# LDO.net
KiCad netlist of a schematic drawn in Altium Designer
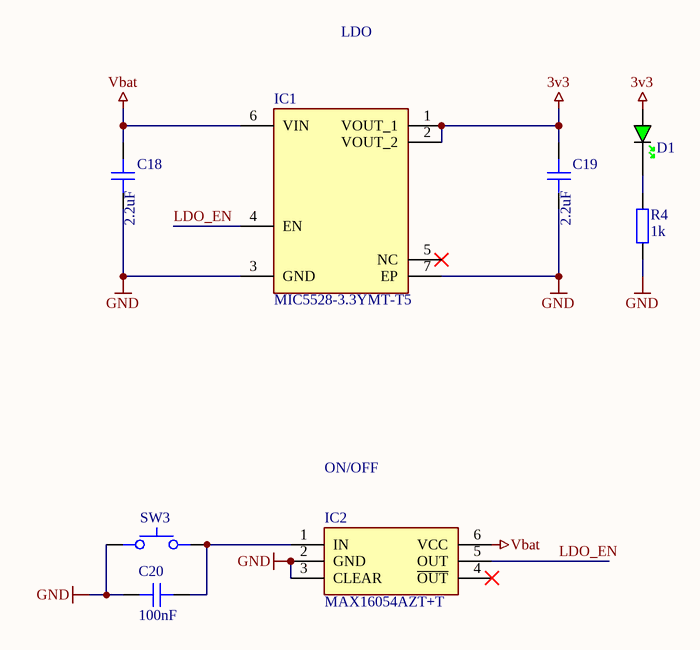
[diagram p0: LDO.SchDoc]

(export (version "E")
  (design (tool "Eeschema 10.0.6"))
  (components
    (comp (ref "C18")
      (value "2.2uF")
      (footprint "CAP_0402")
      (description "Capacitor SMD 0402 10V")
      (fields (field (name "Comment") "C0402_10V"))
      (libsource (lib "Schematic-Lib-PhilsLab") (part "CAP_0402_10V"))
    )
    (comp (ref "C19")
      (value "2.2uF")
      (footprint "CAP_0402")
      (description "Capacitor SMD 0402 10V")
      (fields (field (name "Comment") "C0402_10V"))
      (libsource (lib "Schematic-Lib-PhilsLab") (part "CAP_0402_10V"))
    )
    (comp (ref "C20")
      (value "100nF")
      (footprint "CAP_0402")
      (description "Capacitor SMD 0402 10V")
      (fields (field (name "Comment") "C0402_10V"))
      (libsource (lib "Schematic-Lib-PhilsLab") (part "CAP_0402_10V"))
    )
    (comp (ref "D1")
      (value "GREEN")
      (footprint "LED_0402_GREEN")
      (description "LED 0402 GREEN SMD")
      (libsource (lib "Schematic-Lib-PhilsLab") (part "LED_0402_GREEN"))
    )
    (comp (ref "IC1")
      (value "MIC5528-3.3YMT-T5")
      (footprint "Footprint-Lib-PhilsLab:SON40P120X120X60-7N-D")
      (description "LDO 3v3 500mA")
      (fields (field (name "MOUSER PART NUMBER") "998-MIC5528-3.3YMTT5"))
      (libsource (lib "Schematic-Lib-PhilsLab") (part "MIC5528-3.3YMT-T5"))
    )
    (comp (ref "IC2")
      (value "MAX16054AZT+T")
      (footprint "Footprint-Lib-PhilsLab:SOT95P275X110-6N")
      (description "Integrated Circuit")
      (fields (field (name "MOUSER PART NUMBER") "700-MAX16054AZTT"))
      (libsource (lib "Schematic-Lib-PhilsLab") (part "MAX16054AZT+T"))
    )
    (comp (ref "R4")
      (value "1k")
      (footprint "RES_0402")
      (description "Resistor SMD 0402")
      (fields (field (name "Comment") "R0402"))
      (libsource (lib "Schematic-Lib-PhilsLab") (part "RES_0402"))
    )
    (comp (ref "SW3")
      (value "SKRPANE010")
      (footprint "SKRPANE010")
      (description "Tactile Switch SMD SPST")
      (fields (field (name "MANUFACTURER") "Alps Alpine"))
      (libsource (lib "Schematic-Lib-PhilsLab") (part "SKRPANE010"))
    )
  )
  (nets
    (net (code "1") (name "/LDO_EN") (class "Default")
      (node (ref "IC1") (pin "4") (pinfunction "EN_4") (pintype "passive"))
      (node (ref "IC2") (pin "5") (pinfunction "OUT_5") (pintype "passive"))
    )
    (net (code "2") (name "3v3") (class "Default")
      (node (ref "C19") (pin "2") (pinfunction "2_2") (pintype "passive"))
      (node (ref "D1") (pin "A") (pinfunction "A_A") (pintype "passive"))
      (node (ref "IC1") (pin "1") (pinfunction "VOUT_1_1") (pintype "passive"))
      (node (ref "IC1") (pin "2") (pinfunction "VOUT_2_2") (pintype "passive"))
    )
    (net (code "3") (name "GND") (class "Default")
      (node (ref "C18") (pin "1") (pinfunction "1_1") (pintype "passive"))
      (node (ref "C19") (pin "1") (pinfunction "1_1") (pintype "passive"))
      (node (ref "C20") (pin "2") (pinfunction "2_2") (pintype "passive"))
      (node (ref "IC1") (pin "3") (pinfunction "GND_3") (pintype "passive"))
      (node (ref "IC1") (pin "7") (pinfunction "EP_7") (pintype "passive"))
      (node (ref "IC2") (pin "2") (pinfunction "GND_2") (pintype "passive"))
      (node (ref "IC2") (pin "3") (pinfunction "CLEAR_3") (pintype "passive"))
      (node (ref "R4") (pin "2") (pinfunction "2_2") (pintype "passive"))
      (node (ref "SW3") (pin "12") (pintype "passive"))
    )
    (net (code "4") (name "Net-(D1-PadK)") (class "Default")
      (node (ref "D1") (pin "K") (pinfunction "K_K") (pintype "passive"))
      (node (ref "R4") (pin "1") (pinfunction "1_1") (pintype "passive"))
    )
    (net (code "5") (name "Net-(IC2-IN)") (class "Default")
      (node (ref "C20") (pin "1") (pinfunction "1_1") (pintype "passive"))
      (node (ref "IC2") (pin "1") (pinfunction "IN_1") (pintype "passive"))
      (node (ref "SW3") (pin "34") (pintype "passive"))
    )
    (net (code "6") (name "Vbat") (class "Default")
      (node (ref "C18") (pin "2") (pinfunction "2_2") (pintype "passive"))
      (node (ref "IC1") (pin "6") (pinfunction "VIN_6") (pintype "passive"))
      (node (ref "IC2") (pin "6") (pinfunction "VCC_6") (pintype "passive"))
    )
    (net (code "7") (name "unconnected-(IC1-NC-Pad5)") (class "Default")
      (node (ref "IC1") (pin "5") (pinfunction "NC_5") (pintype "passive+no_connect"))
    )
    (net (code "8") (name "unconnected-(IC2-~{OUT}-Pad4)") (class "Default")
      (node (ref "IC2") (pin "4") (pinfunction "~{OUT}_4") (pintype "passive+no_connect"))
    )
  )
)
